# BQ25570.net
KiCad netlist of a schematic drawn in EAGLE
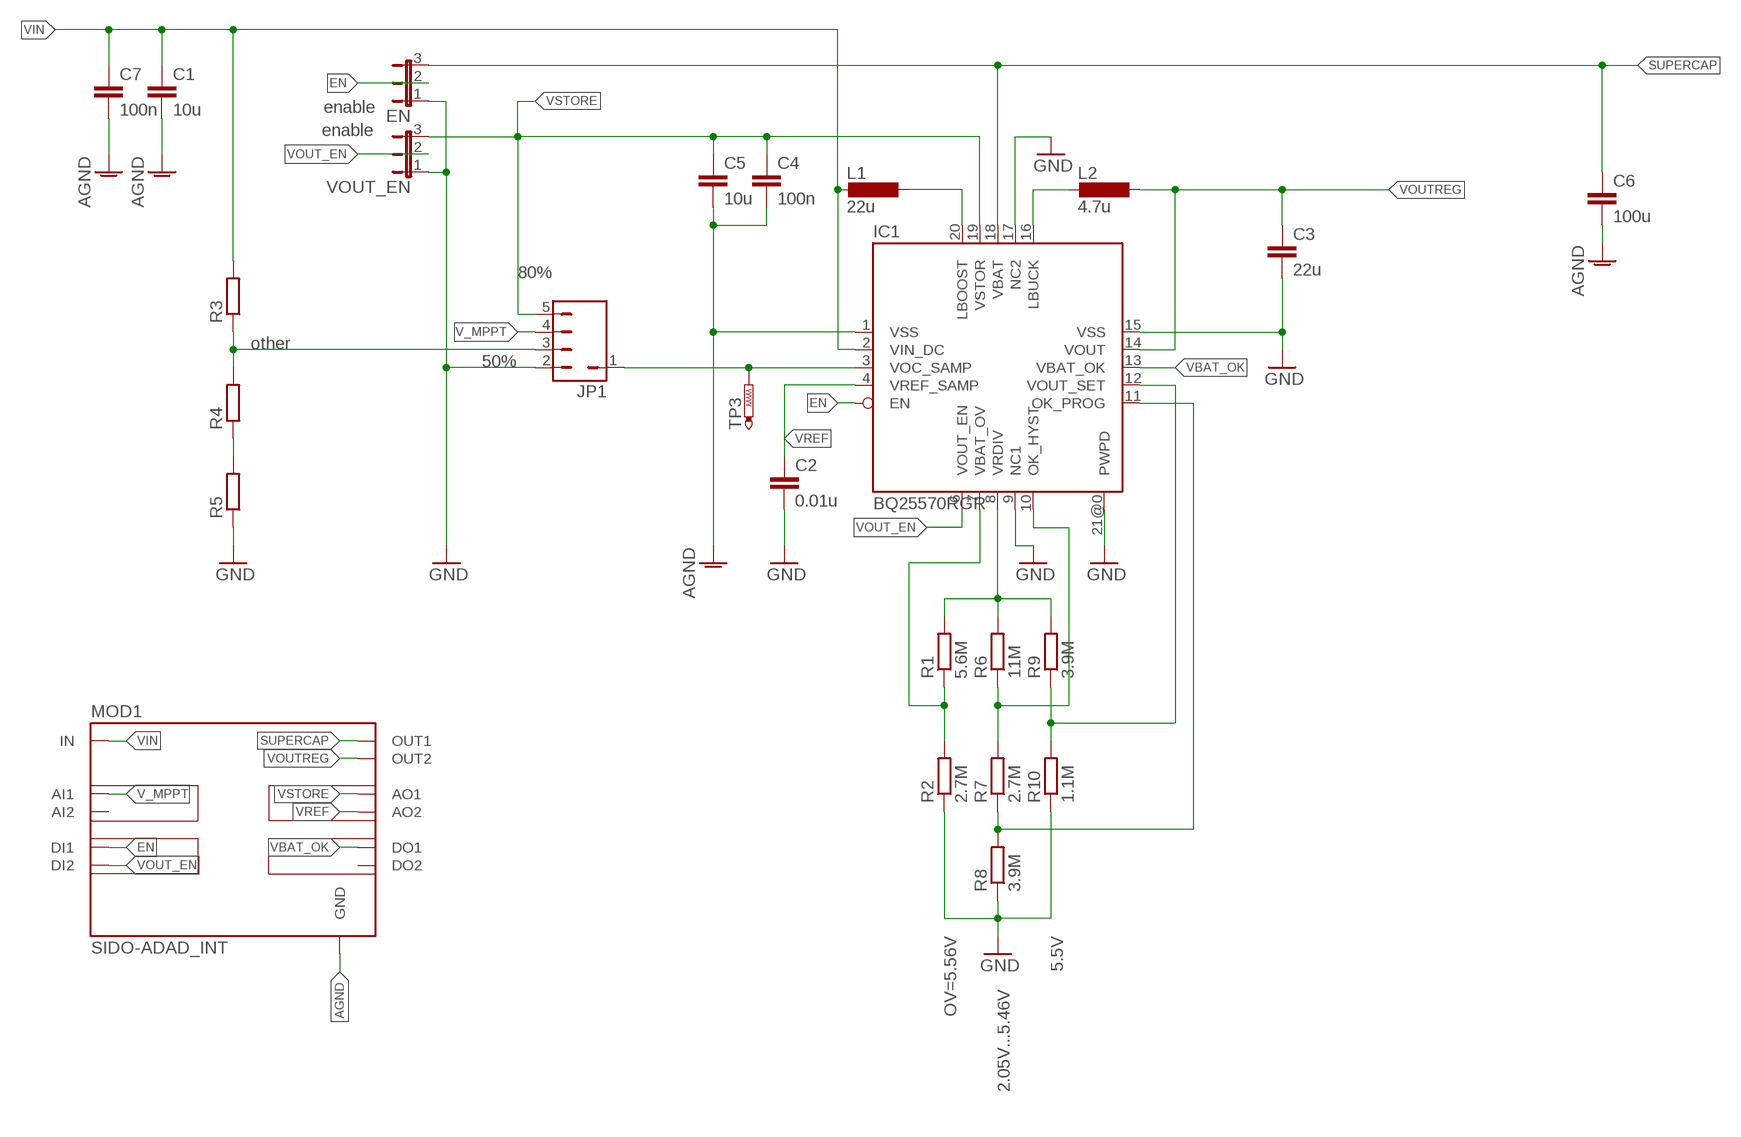
[diagram p0: schematic, sheet 1]

(export (version "E")
  (design (tool "Eeschema 10.0.6"))
  (components
    (comp (ref "C1")
      (value "10u")
      (footprint "eagle-import:C1206K")
      (libsource (lib "eagle-import") (part "C-EUC1206K"))
    )
    (comp (ref "C2")
      (value "0.01u")
      (footprint "eagle-import:C0805K")
      (libsource (lib "eagle-import") (part "C-EUC0805K"))
    )
    (comp (ref "C3")
      (value "22u")
      (footprint "eagle-import:C1206K")
      (libsource (lib "eagle-import") (part "C-EUC1206K"))
    )
    (comp (ref "C4")
      (value "100n")
      (footprint "eagle-import:C0805K")
      (libsource (lib "eagle-import") (part "C-EUC0805K"))
    )
    (comp (ref "C5")
      (value "10u")
      (footprint "eagle-import:C1206K")
      (libsource (lib "eagle-import") (part "C-EUC1206K"))
    )
    (comp (ref "C6")
      (value "100u")
      (footprint "eagle-import:C1206K")
      (libsource (lib "eagle-import") (part "C-EUC1206K"))
    )
    (comp (ref "C7")
      (value "100n")
      (footprint "eagle-import:C0805K")
      (libsource (lib "eagle-import") (part "C-EUC0805K"))
    )
    (comp (ref "EN")
      (value "JP2E")
      (footprint "eagle-import:JP2")
      (libsource (lib "eagle-import") (part "JP2E"))
    )
    (comp (ref "IC1")
      (value "BQ25570RGR")
      (footprint "eagle-import:QFN20")
      (libsource (lib "eagle-import") (part "BQ25570RGR"))
    )
    (comp (ref "JP1")
      (value "JP3Q")
      (footprint "eagle-import:JP1-4")
      (libsource (lib "eagle-import") (part "JP3Q"))
    )
    (comp (ref "L1")
      (value "22u")
      (footprint "eagle-import:L4035M")
      (libsource (lib "eagle-import") (part "L-EUL4035M"))
    )
    (comp (ref "L2")
      (value "4.7u")
      (footprint "eagle-import:L4035M")
      (libsource (lib "eagle-import") (part "L-EUL4035M"))
    )
    (comp (ref "MOD1")
      (value "SIDO-ADAD_INT")
      (footprint "eagle-import:SIDO-ADAD")
      (libsource (lib "eagle-import") (part "SIDO-ADAD_INT"))
    )
    (comp (ref "R1")
      (value "5.6M")
      (footprint "eagle-import:R0805")
      (libsource (lib "eagle-import") (part "R-EU_R0805"))
    )
    (comp (ref "R2")
      (value "2.7M")
      (footprint "eagle-import:R0805")
      (libsource (lib "eagle-import") (part "R-EU_R0805"))
    )
    (comp (ref "R3")
      (value "R-EU_R0805")
      (footprint "eagle-import:R0805")
      (libsource (lib "eagle-import") (part "R-EU_R0805"))
    )
    (comp (ref "R4")
      (value "R-EU_R0805")
      (footprint "eagle-import:R0805")
      (libsource (lib "eagle-import") (part "R-EU_R0805"))
    )
    (comp (ref "R5")
      (value "R-EU_R0805")
      (footprint "eagle-import:R0805")
      (libsource (lib "eagle-import") (part "R-EU_R0805"))
    )
    (comp (ref "R6")
      (value "11M")
      (footprint "eagle-import:R0805")
      (libsource (lib "eagle-import") (part "R-EU_R0805"))
    )
    (comp (ref "R7")
      (value "2.7M")
      (footprint "eagle-import:R0805")
      (libsource (lib "eagle-import") (part "R-EU_R0805"))
    )
    (comp (ref "R8")
      (value "3.9M")
      (footprint "eagle-import:R0805")
      (libsource (lib "eagle-import") (part "R-EU_R0805"))
    )
    (comp (ref "R9")
      (value "3.9M")
      (footprint "eagle-import:R0805")
      (libsource (lib "eagle-import") (part "R-EU_R0805"))
    )
    (comp (ref "R10")
      (value "1.1M")
      (footprint "eagle-import:R0805")
      (libsource (lib "eagle-import") (part "R-EU_R0805"))
    )
    (comp (ref "TP3")
      (value "PTR1B1,27")
      (footprint "eagle-import:B1,27")
      (libsource (lib "eagle-import") (part "PTR1B1,27"))
    )
    (comp (ref "VOUT_EN")
      (value "JP2E")
      (footprint "eagle-import:JP2")
      (libsource (lib "eagle-import") (part "JP2E"))
    )
  )
  (nets
    (net (code "1") (name "AGND") (class "Default")
      (node (ref "C1") (pin "2") (pinfunction "2_2") (pintype "passive"))
      (node (ref "C4") (pin "2") (pinfunction "2_2") (pintype "passive"))
      (node (ref "C5") (pin "2") (pinfunction "2_2") (pintype "passive"))
      (node (ref "C6") (pin "2") (pinfunction "2_2") (pintype "passive"))
      (node (ref "C7") (pin "2") (pinfunction "2_2") (pintype "passive"))
      (node (ref "IC1") (pin "1") (pinfunction "VSS_1") (pintype "power_in"))
      (node (ref "MOD1") (pin "GND1") (pinfunction "GND_GND1") (pintype "power_in"))
      (node (ref "MOD1") (pin "GND2") (pinfunction "GND_GND2") (pintype "power_in"))
      (node (ref "MOD1") (pin "GND3") (pinfunction "GND_GND3") (pintype "power_in"))
      (node (ref "MOD1") (pin "GND4") (pinfunction "GND_GND4") (pintype "power_in"))
    )
    (net (code "2") (name "EN") (class "Default")
      (node (ref "EN") (pin "2") (pinfunction "2_2") (pintype "passive"))
      (node (ref "IC1") (pin "5") (pinfunction "EN_5") (pintype "input"))
      (node (ref "MOD1") (pin "DI1") (pinfunction "DI1_DI1") (pintype "output"))
    )
    (net (code "3") (name "GND") (class "Default")
      (node (ref "C2") (pin "2") (pinfunction "2_2") (pintype "passive"))
      (node (ref "C3") (pin "2") (pinfunction "2_2") (pintype "passive"))
      (node (ref "EN") (pin "1") (pinfunction "1_1") (pintype "passive"))
      (node (ref "IC1") (pin "15") (pinfunction "VSS_15") (pintype "power_in"))
      (node (ref "IC1") (pin "17") (pinfunction "NC2_17") (pintype "power_in"))
      (node (ref "IC1") (pin "21@0") (pinfunction "PWPD_21@0") (pintype "power_in"))
      (node (ref "IC1") (pin "9") (pinfunction "NC1_9") (pintype "power_in"))
      (node (ref "JP1") (pin "2") (pinfunction "2_2") (pintype "passive"))
      (node (ref "R10") (pin "1") (pinfunction "1_1") (pintype "passive"))
      (node (ref "R2") (pin "1") (pinfunction "1_1") (pintype "passive"))
      (node (ref "R5") (pin "1") (pinfunction "1_1") (pintype "passive"))
      (node (ref "R8") (pin "1") (pinfunction "1_1") (pintype "passive"))
      (node (ref "VOUT_EN") (pin "1") (pinfunction "1_1") (pintype "passive"))
    )
    (net (code "4") (name "Net-(IC1-LBOOST)") (class "Default")
      (node (ref "IC1") (pin "20") (pinfunction "LBOOST_20") (pintype "power_in"))
      (node (ref "L1") (pin "1") (pinfunction "1_1") (pintype "passive"))
    )
    (net (code "5") (name "Net-(IC1-LBUCK)") (class "Default")
      (node (ref "IC1") (pin "16") (pinfunction "LBUCK_16") (pintype "power_in"))
      (node (ref "L2") (pin "2") (pinfunction "2_2") (pintype "passive"))
    )
    (net (code "6") (name "Net-(IC1-OK_HYST)") (class "Default")
      (node (ref "IC1") (pin "10") (pinfunction "OK_HYST_10") (pintype "input"))
      (node (ref "R6") (pin "1") (pinfunction "1_1") (pintype "passive"))
      (node (ref "R7") (pin "2") (pinfunction "2_2") (pintype "passive"))
    )
    (net (code "7") (name "Net-(IC1-OK_PROG)") (class "Default")
      (node (ref "IC1") (pin "11") (pinfunction "OK_PROG_11") (pintype "input"))
      (node (ref "R7") (pin "1") (pinfunction "1_1") (pintype "passive"))
      (node (ref "R8") (pin "2") (pinfunction "2_2") (pintype "passive"))
    )
    (net (code "8") (name "Net-(IC1-VBAT_OV)") (class "Default")
      (node (ref "IC1") (pin "7") (pinfunction "VBAT_OV_7") (pintype "input"))
      (node (ref "R1") (pin "1") (pinfunction "1_1") (pintype "passive"))
      (node (ref "R2") (pin "2") (pinfunction "2_2") (pintype "passive"))
    )
    (net (code "9") (name "Net-(IC1-VOC_SAMP)") (class "Default")
      (node (ref "IC1") (pin "3") (pinfunction "VOC_SAMP_3") (pintype "input"))
      (node (ref "JP1") (pin "1") (pinfunction "1_1") (pintype "passive"))
      (node (ref "TP3") (pin "TP") (pinfunction "TP_TP") (pintype "input"))
    )
    (net (code "10") (name "Net-(IC1-VOUT_SET)") (class "Default")
      (node (ref "IC1") (pin "12") (pinfunction "VOUT_SET_12") (pintype "input"))
      (node (ref "R10") (pin "2") (pinfunction "2_2") (pintype "passive"))
      (node (ref "R9") (pin "1") (pinfunction "1_1") (pintype "passive"))
    )
    (net (code "11") (name "Net-(IC1-VRDIV)") (class "Default")
      (node (ref "IC1") (pin "8") (pinfunction "VRDIV_8") (pintype "bidirectional"))
      (node (ref "R1") (pin "2") (pinfunction "2_2") (pintype "passive"))
      (node (ref "R6") (pin "2") (pinfunction "2_2") (pintype "passive"))
      (node (ref "R9") (pin "2") (pinfunction "2_2") (pintype "passive"))
    )
    (net (code "12") (name "Net-(JP1-Pad3)") (class "Default")
      (node (ref "JP1") (pin "3") (pinfunction "3_3") (pintype "passive"))
      (node (ref "R3") (pin "1") (pinfunction "1_1") (pintype "passive"))
      (node (ref "R4") (pin "2") (pinfunction "2_2") (pintype "passive"))
    )
    (net (code "13") (name "Net-(R4-Pad1)") (class "Default")
      (node (ref "R4") (pin "1") (pinfunction "1_1") (pintype "passive"))
      (node (ref "R5") (pin "2") (pinfunction "2_2") (pintype "passive"))
    )
    (net (code "14") (name "SUPERCAP") (class "Default")
      (node (ref "C6") (pin "1") (pinfunction "1_1") (pintype "passive"))
      (node (ref "EN") (pin "3") (pinfunction "3_3") (pintype "passive"))
      (node (ref "IC1") (pin "18") (pinfunction "VBAT_18") (pintype "power_in"))
      (node (ref "MOD1") (pin "OUT1_1") (pinfunction "OUT1_OUT1_1") (pintype "input"))
      (node (ref "MOD1") (pin "OUT1_2") (pinfunction "OUT1_OUT1_2") (pintype "input"))
      (node (ref "MOD1") (pin "OUT1_3") (pinfunction "OUT1_OUT1_3") (pintype "input"))
      (node (ref "MOD1") (pin "OUT1_4") (pinfunction "OUT1_OUT1_4") (pintype "input"))
    )
    (net (code "15") (name "VBAT_OK") (class "Default")
      (node (ref "IC1") (pin "13") (pinfunction "VBAT_OK_13") (pintype "output"))
      (node (ref "MOD1") (pin "DO1") (pinfunction "DO1_DO1") (pintype "input"))
    )
    (net (code "16") (name "VIN") (class "Default")
      (node (ref "C1") (pin "1") (pinfunction "1_1") (pintype "passive"))
      (node (ref "C7") (pin "1") (pinfunction "1_1") (pintype "passive"))
      (node (ref "IC1") (pin "2") (pinfunction "VIN_DC_2") (pintype "power_in"))
      (node (ref "L1") (pin "2") (pinfunction "2_2") (pintype "passive"))
      (node (ref "MOD1") (pin "IN1") (pinfunction "IN_IN1") (pintype "output"))
      (node (ref "MOD1") (pin "IN2") (pinfunction "IN_IN2") (pintype "output"))
      (node (ref "MOD1") (pin "IN3") (pinfunction "IN_IN3") (pintype "output"))
      (node (ref "MOD1") (pin "IN4") (pinfunction "IN_IN4") (pintype "output"))
      (node (ref "R3") (pin "2") (pinfunction "2_2") (pintype "passive"))
    )
    (net (code "17") (name "VOUTREG") (class "Default")
      (node (ref "C3") (pin "1") (pinfunction "1_1") (pintype "passive"))
      (node (ref "IC1") (pin "14") (pinfunction "VOUT_14") (pintype "power_in"))
      (node (ref "L2") (pin "1") (pinfunction "1_1") (pintype "passive"))
      (node (ref "MOD1") (pin "OUT2_1") (pinfunction "OUT2_OUT2_1") (pintype "input"))
      (node (ref "MOD1") (pin "OUT2_2") (pinfunction "OUT2_OUT2_2") (pintype "input"))
      (node (ref "MOD1") (pin "OUT2_3") (pinfunction "OUT2_OUT2_3") (pintype "input"))
      (node (ref "MOD1") (pin "OUT2_4") (pinfunction "OUT2_OUT2_4") (pintype "input"))
    )
    (net (code "18") (name "VOUT_EN") (class "Default")
      (node (ref "IC1") (pin "6") (pinfunction "VOUT_EN_6") (pintype "input"))
      (node (ref "MOD1") (pin "DI2") (pinfunction "DI2_DI2") (pintype "output"))
      (node (ref "VOUT_EN") (pin "2") (pinfunction "2_2") (pintype "passive"))
    )
    (net (code "19") (name "VREF") (class "Default")
      (node (ref "C2") (pin "1") (pinfunction "1_1") (pintype "passive"))
      (node (ref "IC1") (pin "4") (pinfunction "VREF_SAMP_4") (pintype "input"))
      (node (ref "MOD1") (pin "AO2") (pinfunction "AO2_AO2") (pintype "input"))
    )
    (net (code "20") (name "VSTORE") (class "Default")
      (node (ref "C4") (pin "1") (pinfunction "1_1") (pintype "passive"))
      (node (ref "C5") (pin "1") (pinfunction "1_1") (pintype "passive"))
      (node (ref "IC1") (pin "19") (pinfunction "VSTOR_19") (pintype "bidirectional"))
      (node (ref "JP1") (pin "5") (pinfunction "5_5") (pintype "passive"))
      (node (ref "MOD1") (pin "AO1") (pinfunction "AO1_AO1") (pintype "input"))
      (node (ref "VOUT_EN") (pin "3") (pinfunction "3_3") (pintype "passive"))
    )
    (net (code "21") (name "V_MPPT") (class "Default")
      (node (ref "JP1") (pin "4") (pinfunction "4_4") (pintype "passive"))
      (node (ref "MOD1") (pin "AI1") (pinfunction "AI1_AI1") (pintype "output"))
    )
    (net (code "22") (name "unconnected-(MOD1-PadAI2)") (class "Default")
      (node (ref "MOD1") (pin "AI2") (pinfunction "AI2_AI2") (pintype "output"))
    )
    (net (code "23") (name "unconnected-(MOD1-PadDO2)") (class "Default")
      (node (ref "MOD1") (pin "DO2") (pinfunction "DO2_DO2") (pintype "input"))
    )
  )
)
